# tx_board.net
KiCad netlist of a schematic drawn in EAGLE
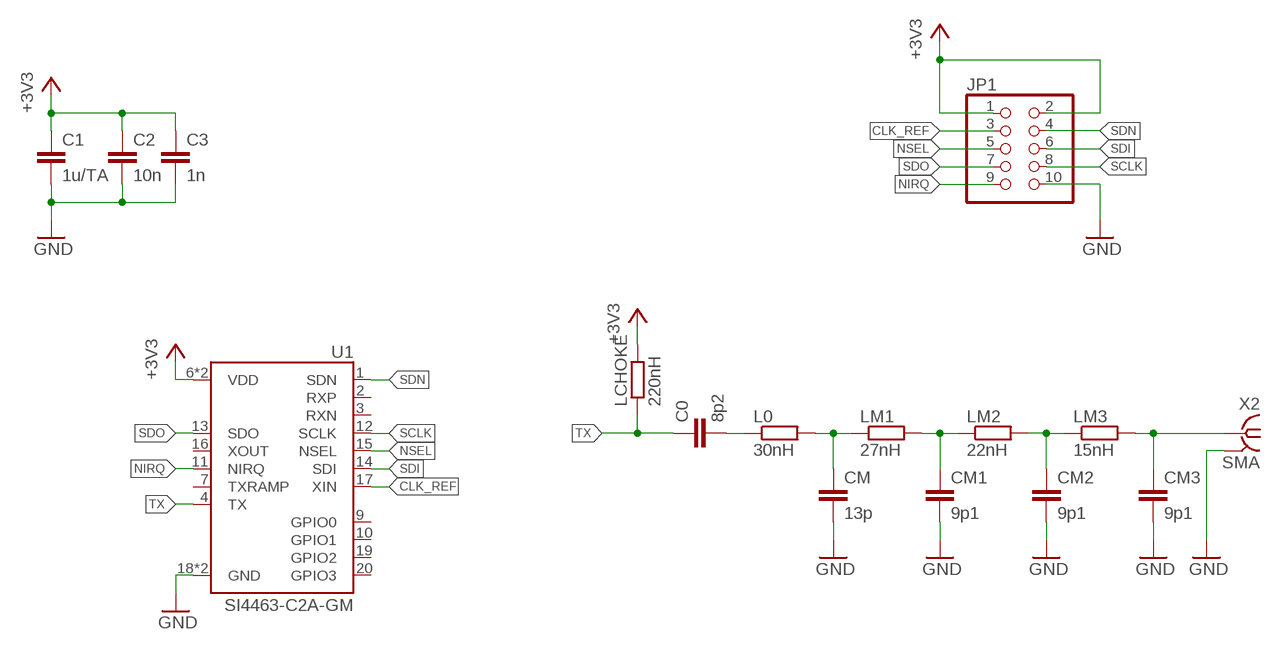
[diagram p0: schematic, sheet 1]

(export (version "E")
  (design (tool "Eeschema 10.0.6"))
  (components
    (comp (ref "C0")
      (value "8p2")
      (footprint "eagle-import:C0805")
      (libsource (lib "eagle-import") (part "C-EUC0805"))
    )
    (comp (ref "C1")
      (value "1u/TA")
      (footprint "eagle-import:C1206")
      (libsource (lib "eagle-import") (part "C-EUC1206"))
    )
    (comp (ref "C2")
      (value "10n")
      (footprint "eagle-import:C0805")
      (libsource (lib "eagle-import") (part "C-EUC0805"))
    )
    (comp (ref "C3")
      (value "1n")
      (footprint "eagle-import:C0805")
      (libsource (lib "eagle-import") (part "C-EUC0805"))
    )
    (comp (ref "CM")
      (value "13p")
      (footprint "eagle-import:C0805")
      (libsource (lib "eagle-import") (part "C-EUC0805"))
    )
    (comp (ref "CM1")
      (value "9p1")
      (footprint "eagle-import:C0805")
      (libsource (lib "eagle-import") (part "C-EUC0805"))
    )
    (comp (ref "CM2")
      (value "9p1")
      (footprint "eagle-import:C0805")
      (libsource (lib "eagle-import") (part "C-EUC0805"))
    )
    (comp (ref "CM3")
      (value "9p1")
      (footprint "eagle-import:C0805")
      (libsource (lib "eagle-import") (part "C-EUC0805"))
    )
    (comp (ref "JP1")
      (value "PINHD-2X5/90")
      (footprint "eagle-import:2X05_90")
      (libsource (lib "eagle-import") (part "PINHD-2X5/90"))
    )
    (comp (ref "L0")
      (value "30nH")
      (footprint "eagle-import:R0805")
      (libsource (lib "eagle-import") (part "R-EU_R0805"))
    )
    (comp (ref "LCHOKE")
      (value "220nH")
      (footprint "eagle-import:R0805")
      (libsource (lib "eagle-import") (part "R-EU_R0805"))
    )
    (comp (ref "LM1")
      (value "27nH")
      (footprint "eagle-import:R0805")
      (libsource (lib "eagle-import") (part "R-EU_R0805"))
    )
    (comp (ref "LM2")
      (value "22nH")
      (footprint "eagle-import:R0805")
      (libsource (lib "eagle-import") (part "R-EU_R0805"))
    )
    (comp (ref "LM3")
      (value "15nH")
      (footprint "eagle-import:R0805")
      (libsource (lib "eagle-import") (part "R-EU_R0805"))
    )
    (comp (ref "U1")
      (value "SI4463-C2A-GM")
      (footprint "eagle-import:QFN50P400X400X90-20N")
      (fields (field (name "MF") "Silicon Labs"))
      (libsource (lib "eagle-import") (part "SI4463-C2A-GM"))
    )
    (comp (ref "X2")
      (value "SMA")
      (footprint "eagle-import:J502-ND-142-0701-871_876")
      (fields (field (name "MF") "JOHNSON COMPONENTS") (field (name "MPN") "142-0701-871"))
      (libsource (lib "eagle-import") (part "SMA-142-0701-871/876"))
    )
  )
  (nets
    (net (code "1") (name "+3V3") (class "Default")
      (node (ref "C1") (pin "1") (pinfunction "1_1") (pintype "passive"))
      (node (ref "C2") (pin "1") (pinfunction "1_1") (pintype "passive"))
      (node (ref "C3") (pin "1") (pinfunction "1_1") (pintype "passive"))
      (node (ref "JP1") (pin "1") (pinfunction "1_1") (pintype "passive"))
      (node (ref "JP1") (pin "2") (pinfunction "2_2") (pintype "passive"))
      (node (ref "LCHOKE") (pin "2") (pinfunction "2_2") (pintype "passive"))
      (node (ref "U1") (pin "6") (pinfunction "VDD_6") (pintype "power_in"))
      (node (ref "U1") (pin "8") (pinfunction "VDD_8") (pintype "power_in"))
    )
    (net (code "2") (name "CLK_REF") (class "Default")
      (node (ref "JP1") (pin "3") (pinfunction "3_3") (pintype "passive"))
      (node (ref "U1") (pin "17") (pinfunction "XIN_17") (pintype "input"))
    )
    (net (code "3") (name "GND") (class "Default")
      (node (ref "C1") (pin "2") (pinfunction "2_2") (pintype "passive"))
      (node (ref "C2") (pin "2") (pinfunction "2_2") (pintype "passive"))
      (node (ref "C3") (pin "2") (pinfunction "2_2") (pintype "passive"))
      (node (ref "CM") (pin "2") (pinfunction "2_2") (pintype "passive"))
      (node (ref "CM1") (pin "2") (pinfunction "2_2") (pintype "passive"))
      (node (ref "CM2") (pin "2") (pinfunction "2_2") (pintype "passive"))
      (node (ref "CM3") (pin "2") (pinfunction "2_2") (pintype "passive"))
      (node (ref "JP1") (pin "10") (pinfunction "10_10") (pintype "passive"))
      (node (ref "U1") (pin "18") (pinfunction "GND_18") (pintype "power_in"))
      (node (ref "U1") (pin "21") (pinfunction "GND_21") (pintype "power_in"))
      (node (ref "X2") (pin "G@1") (pinfunction "2_G@1") (pintype "passive"))
      (node (ref "X2") (pin "G@2") (pinfunction "2_G@2") (pintype "passive"))
      (node (ref "X2") (pin "G@3") (pinfunction "2_G@3") (pintype "passive"))
      (node (ref "X2") (pin "G@4") (pinfunction "2_G@4") (pintype "passive"))
    )
    (net (code "4") (name "NIRQ") (class "Default")
      (node (ref "JP1") (pin "9") (pinfunction "9_9") (pintype "passive"))
      (node (ref "U1") (pin "11") (pinfunction "NIRQ_11") (pintype "output"))
    )
    (net (code "5") (name "NSEL") (class "Default")
      (node (ref "JP1") (pin "5") (pinfunction "5_5") (pintype "passive"))
      (node (ref "U1") (pin "15") (pinfunction "NSEL_15") (pintype "input"))
    )
    (net (code "6") (name "Net-(C0-Pad2)") (class "Default")
      (node (ref "C0") (pin "2") (pinfunction "2_2") (pintype "passive"))
      (node (ref "L0") (pin "1") (pinfunction "1_1") (pintype "passive"))
    )
    (net (code "7") (name "Net-(CM-Pad1)") (class "Default")
      (node (ref "CM") (pin "1") (pinfunction "1_1") (pintype "passive"))
      (node (ref "L0") (pin "2") (pinfunction "2_2") (pintype "passive"))
      (node (ref "LM1") (pin "1") (pinfunction "1_1") (pintype "passive"))
    )
    (net (code "8") (name "Net-(CM1-Pad1)") (class "Default")
      (node (ref "CM1") (pin "1") (pinfunction "1_1") (pintype "passive"))
      (node (ref "LM1") (pin "2") (pinfunction "2_2") (pintype "passive"))
      (node (ref "LM2") (pin "1") (pinfunction "1_1") (pintype "passive"))
    )
    (net (code "9") (name "Net-(CM2-Pad1)") (class "Default")
      (node (ref "CM2") (pin "1") (pinfunction "1_1") (pintype "passive"))
      (node (ref "LM2") (pin "2") (pinfunction "2_2") (pintype "passive"))
      (node (ref "LM3") (pin "1") (pinfunction "1_1") (pintype "passive"))
    )
    (net (code "10") (name "Net-(CM3-Pad1)") (class "Default")
      (node (ref "CM3") (pin "1") (pinfunction "1_1") (pintype "passive"))
      (node (ref "LM3") (pin "2") (pinfunction "2_2") (pintype "passive"))
      (node (ref "X2") (pin "1") (pinfunction "1_1") (pintype "passive"))
    )
    (net (code "11") (name "SCLK") (class "Default")
      (node (ref "JP1") (pin "8") (pinfunction "8_8") (pintype "passive"))
      (node (ref "U1") (pin "12") (pinfunction "SCLK_12") (pintype "input"))
    )
    (net (code "12") (name "SDI") (class "Default")
      (node (ref "JP1") (pin "6") (pinfunction "6_6") (pintype "passive"))
      (node (ref "U1") (pin "14") (pinfunction "SDI_14") (pintype "input"))
    )
    (net (code "13") (name "SDN") (class "Default")
      (node (ref "JP1") (pin "4") (pinfunction "4_4") (pintype "passive"))
      (node (ref "U1") (pin "1") (pinfunction "SDN_1") (pintype "input"))
    )
    (net (code "14") (name "SDO") (class "Default")
      (node (ref "JP1") (pin "7") (pinfunction "7_7") (pintype "passive"))
      (node (ref "U1") (pin "13") (pinfunction "SDO_13") (pintype "output"))
    )
    (net (code "15") (name "TX") (class "Default")
      (node (ref "C0") (pin "1") (pinfunction "1_1") (pintype "passive"))
      (node (ref "LCHOKE") (pin "1") (pinfunction "1_1") (pintype "passive"))
      (node (ref "U1") (pin "4") (pinfunction "TX_4") (pintype "output"))
    )
    (net (code "16") (name "unconnected-(U1-GPIO0-Pad9)") (class "Default")
      (node (ref "U1") (pin "9") (pinfunction "GPIO0_9") (pintype "bidirectional"))
    )
    (net (code "17") (name "unconnected-(U1-GPIO1-Pad10)") (class "Default")
      (node (ref "U1") (pin "10") (pinfunction "GPIO1_10") (pintype "bidirectional"))
    )
    (net (code "18") (name "unconnected-(U1-GPIO2-Pad19)") (class "Default")
      (node (ref "U1") (pin "19") (pinfunction "GPIO2_19") (pintype "bidirectional"))
    )
    (net (code "19") (name "unconnected-(U1-GPIO3-Pad20)") (class "Default")
      (node (ref "U1") (pin "20") (pinfunction "GPIO3_20") (pintype "bidirectional"))
    )
    (net (code "20") (name "unconnected-(U1-RXN-Pad3)") (class "Default")
      (node (ref "U1") (pin "3") (pinfunction "RXN_3") (pintype "input"))
    )
    (net (code "21") (name "unconnected-(U1-RXP-Pad2)") (class "Default")
      (node (ref "U1") (pin "2") (pinfunction "RXP_2") (pintype "input"))
    )
    (net (code "22") (name "unconnected-(U1-TXRAMP-Pad7)") (class "Default")
      (node (ref "U1") (pin "7") (pinfunction "TXRAMP_7") (pintype "output"))
    )
    (net (code "23") (name "unconnected-(U1-XOUT-Pad16)") (class "Default")
      (node (ref "U1") (pin "16") (pinfunction "XOUT_16") (pintype "output"))
    )
  )
)
